# usbminib.net
KiCad netlist of a schematic drawn in EAGLE
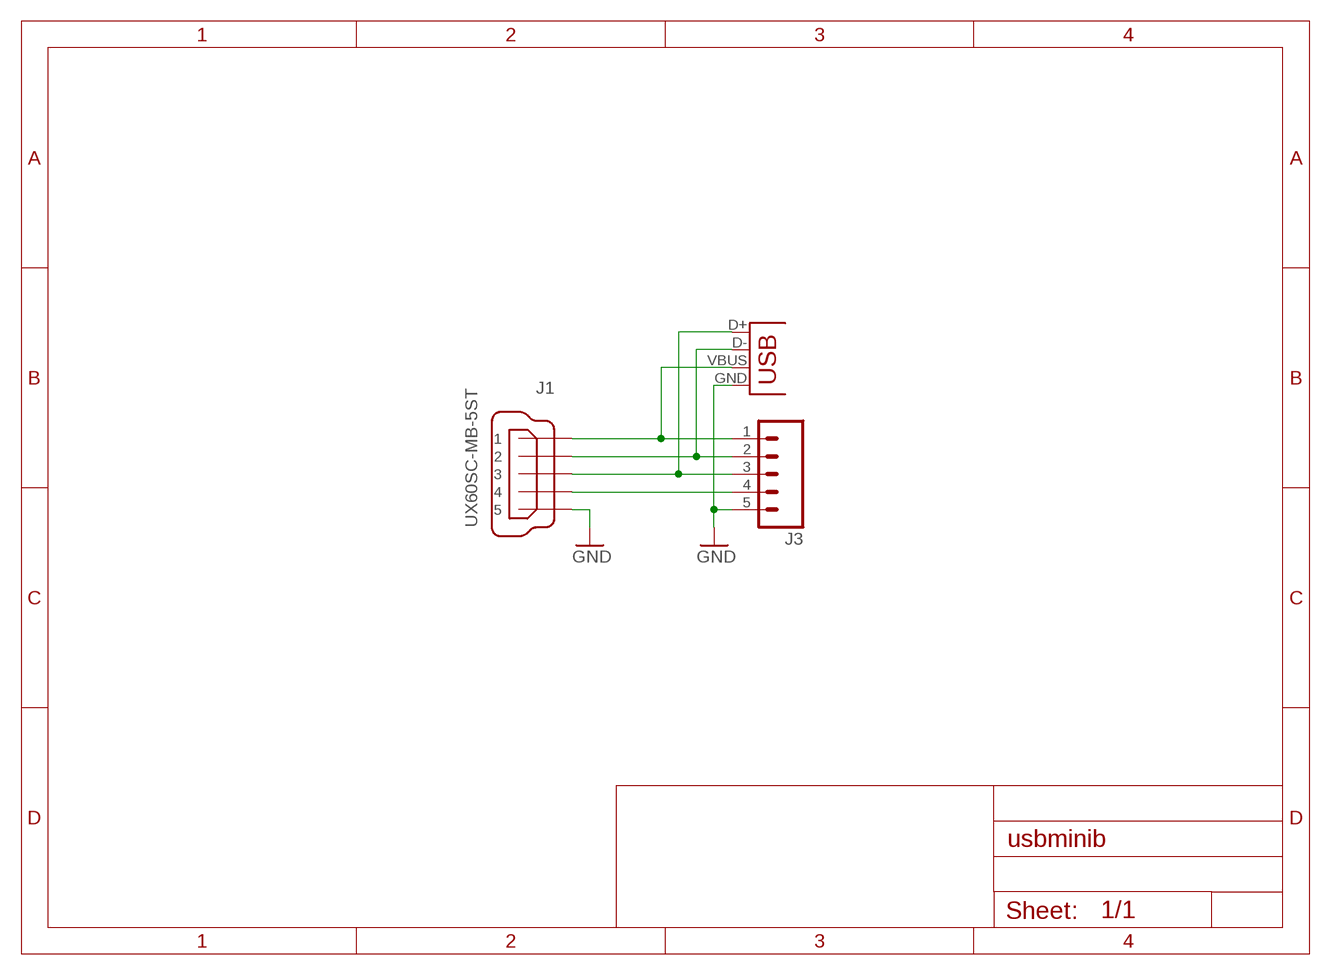
[diagram p0: schematic, sheet 1]

(export (version "E")
  (design (tool "Eeschema 10.0.6"))
  (components
    (comp (ref "J1")
      (value "UX60SC-MB-5ST")
      (footprint "eagle-import:UX60SC-MB-5ST")
      (libsource (lib "eagle-import") (part "UX60SC-MB-5ST"))
    )
    (comp (ref "J2")
      (value "USB-A-H")
      (footprint "eagle-import:USB-A-H")
      (libsource (lib "eagle-import") (part "USB-A-H"))
    )
    (comp (ref "J3")
      (value "M05PTH")
      (footprint "eagle-import:1X05")
      (libsource (lib "eagle-import") (part "M05PTH"))
    )
  )
  (nets
    (net (code "1") (name "GND") (class "Default")
      (node (ref "J1") (pin "5") (pinfunction "5_5") (pintype "input"))
      (node (ref "J2") (pin "GND") (pinfunction "GND_GND") (pintype "bidirectional"))
      (node (ref "J3") (pin "5") (pinfunction "5_5") (pintype "passive"))
    )
    (net (code "2") (name "Net-(J1-Pad1)") (class "Default")
      (node (ref "J1") (pin "1") (pinfunction "1_1") (pintype "input"))
      (node (ref "J2") (pin "VBUS") (pinfunction "VBUS_VBUS") (pintype "bidirectional"))
      (node (ref "J3") (pin "1") (pinfunction "1_1") (pintype "passive"))
    )
    (net (code "3") (name "Net-(J1-Pad2)") (class "Default")
      (node (ref "J1") (pin "2") (pinfunction "2_2") (pintype "input"))
      (node (ref "J2") (pin "D-") (pinfunction "D-_D-") (pintype "bidirectional"))
      (node (ref "J3") (pin "2") (pinfunction "2_2") (pintype "passive"))
    )
    (net (code "4") (name "Net-(J1-Pad3)") (class "Default")
      (node (ref "J1") (pin "3") (pinfunction "3_3") (pintype "input"))
      (node (ref "J2") (pin "D+") (pinfunction "D+_D+") (pintype "bidirectional"))
      (node (ref "J3") (pin "3") (pinfunction "3_3") (pintype "passive"))
    )
    (net (code "5") (name "Net-(J1-Pad4)") (class "Default")
      (node (ref "J1") (pin "4") (pinfunction "4_4") (pintype "input"))
      (node (ref "J3") (pin "4") (pinfunction "4_4") (pintype "passive"))
    )
  )
)
